# 1_P1.net
KiCad netlist of a schematic drawn in Altium Designer
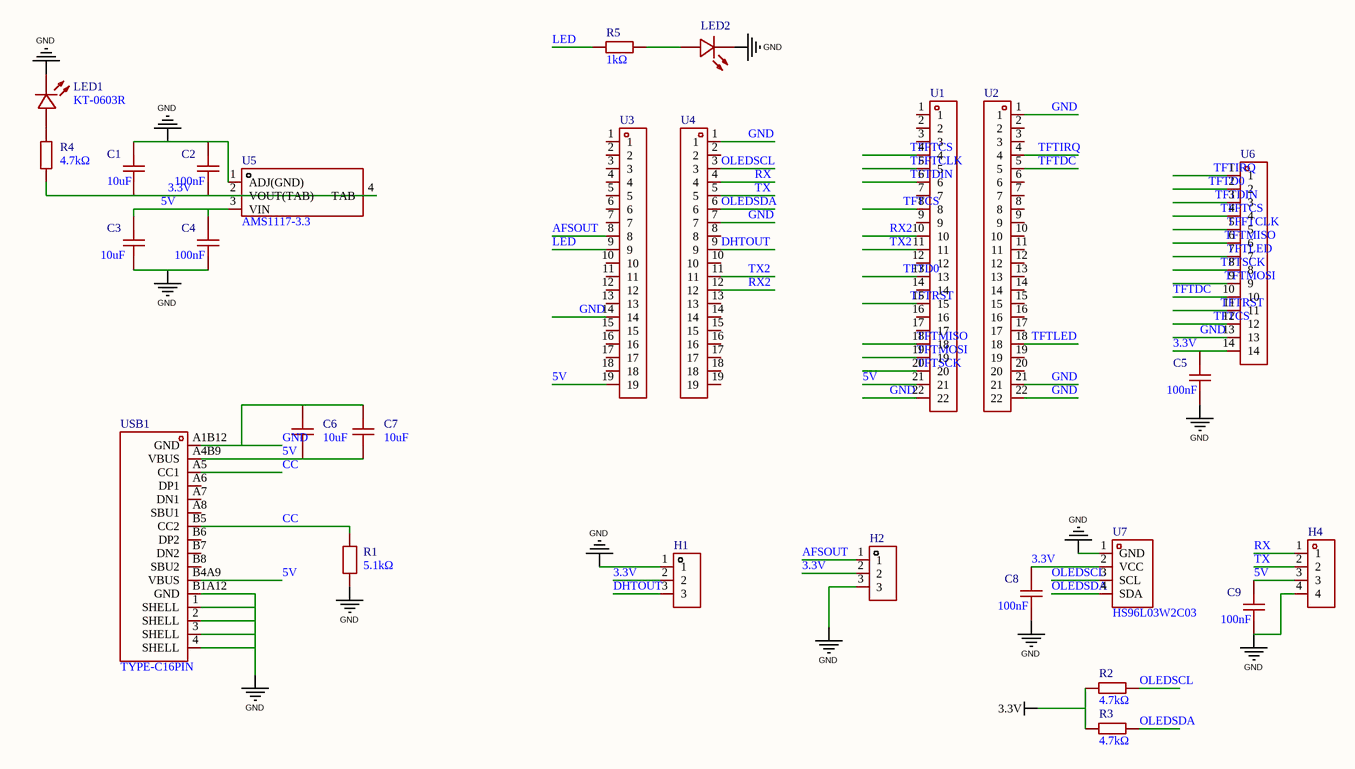
[diagram p0: 1_P1.schdoc]

(export (version "E")
  (design (tool "Eeschema 10.0.6"))
  (components
    (comp (ref "C1")
      (value "10uF")
      (footprint "C0603")
      (fields
        (field (name "MANUFACTURER") "SAMSUNG(三星)")
        (field (name "MANUFACTURER PART") "CL10A106KP8NNNC")
        (field (name "TOLERANCE") "±10%")
      )
      (libsource (lib "altium-import") (part "root_1_CL10A106KP8NNNC_"))
    )
    (comp (ref "C2")
      (value "100nF")
      (footprint "C0603")
      (fields
        (field (name "MANUFACTURER") "YAGEO(国巨)")
        (field (name "MANUFACTURER PART") "CC0603KRX7R9BB104")
        (field (name "TOLERANCE") "±10%")
      )
      (libsource (lib "altium-import") (part "root_1_CC0603KRX7R9BB104_"))
    )
    (comp (ref "C3")
      (value "10uF")
      (footprint "C0603")
      (fields
        (field (name "MANUFACTURER") "SAMSUNG(三星)")
        (field (name "MANUFACTURER PART") "CL10A106KP8NNNC")
        (field (name "TOLERANCE") "±10%")
      )
      (libsource (lib "altium-import") (part "root_1_CL10A106KP8NNNC_"))
    )
    (comp (ref "C4")
      (value "100nF")
      (footprint "C0603")
      (fields
        (field (name "MANUFACTURER") "YAGEO(国巨)")
        (field (name "MANUFACTURER PART") "CC0603KRX7R9BB104")
        (field (name "TOLERANCE") "±10%")
      )
      (libsource (lib "altium-import") (part "root_1_CC0603KRX7R9BB104_"))
    )
    (comp (ref "C5")
      (value "100nF")
      (footprint "C0603")
      (fields
        (field (name "MANUFACTURER") "YAGEO(国巨)")
        (field (name "MANUFACTURER PART") "CC0603KRX7R9BB104")
        (field (name "TOLERANCE") "±10%")
      )
      (libsource (lib "altium-import") (part "root_1_CC0603KRX7R9BB104_"))
    )
    (comp (ref "C6")
      (value "10uF")
      (footprint "C0603")
      (fields
        (field (name "MANUFACTURER") "SAMSUNG(三星)")
        (field (name "MANUFACTURER PART") "CL10A106KP8NNNC")
        (field (name "TOLERANCE") "±10%")
      )
      (libsource (lib "altium-import") (part "root_3_CL10A106KP8NNNC_"))
    )
    (comp (ref "C7")
      (value "10uF")
      (footprint "C0603")
      (fields
        (field (name "MANUFACTURER") "SAMSUNG(三星)")
        (field (name "MANUFACTURER PART") "CL10A106KP8NNNC")
        (field (name "TOLERANCE") "±10%")
      )
      (libsource (lib "altium-import") (part "root_3_CL10A106KP8NNNC_"))
    )
    (comp (ref "C8")
      (value "100nF")
      (footprint "C0603")
      (fields
        (field (name "MANUFACTURER") "YAGEO(国巨)")
        (field (name "MANUFACTURER PART") "CC0603KRX7R9BB104")
        (field (name "TOLERANCE") "±10%")
      )
      (libsource (lib "altium-import") (part "root_1_CC0603KRX7R9BB104_"))
    )
    (comp (ref "C9")
      (value "100nF")
      (footprint "C0603")
      (fields
        (field (name "MANUFACTURER") "YAGEO(国巨)")
        (field (name "MANUFACTURER PART") "CC0603KRX7R9BB104")
        (field (name "TOLERANCE") "±10%")
      )
      (libsource (lib "altium-import") (part "root_1_CC0603KRX7R9BB104_"))
    )
    (comp (ref "H1")
      (value "PM254V-11-03-H85")
      (footprint "HDR-TH_3P-P2.54-V-F")
      (fields (field (name "MANUFACTURER") "XFCN(兴飞)"))
      (libsource (lib "altium-import") (part "root_0_PM254V-11-03-H85_"))
    )
    (comp (ref "H2")
      (value "PM254V-11-03-H85")
      (footprint "HDR-TH_3P-P2.54-V-F")
      (fields (field (name "MANUFACTURER") "XFCN(兴飞)"))
      (libsource (lib "altium-import") (part "root_0_PM254V-11-03-H85_"))
    )
    (comp (ref "H4")
      (value "PZ254V-11-04P")
      (footprint "HDR-TH_4P-P2.54-V-M")
      (fields (field (name "MANUFACTURER") "XFCN(兴飞)"))
      (libsource (lib "altium-import") (part "root_0_PZ254V-11-04P_"))
    )
    (comp (ref "LED1")
      (value "KT-0603R")
      (footprint "LED0603-RD")
      (fields (field (name "MANUFACTURER") "KENTO"))
      (libsource (lib "altium-import") (part "root_3_KT-0603R_"))
    )
    (comp (ref "LED2")
      (value "KT-0603R")
      (footprint "LED0603-RD")
      (fields (field (name "MANUFACTURER") "KENTO"))
      (libsource (lib "altium-import") (part "root_2_KT-0603R_"))
    )
    (comp (ref "R1")
      (value "5.1kΩ")
      (footprint "R0603")
      (fields
        (field (name "MANUFACTURER") "FOJAN(富捷)")
        (field (name "MANUFACTURER PART") "FRC0603F5101TS")
        (field (name "TOLERANCE") "±1%")
      )
      (libsource (lib "altium-import") (part "root_1_mirrored_FRC0603F5101TS_"))
    )
    (comp (ref "R2")
      (value "4.7kΩ")
      (footprint "R0603")
      (fields
        (field (name "MANUFACTURER") "UNI-ROYAL(厚声)")
        (field (name "MANUFACTURER PART") "0603WAF4701T5E")
        (field (name "TOLERANCE") "±1%")
      )
      (libsource (lib "altium-import") (part "root_2_0603WAF4701T5E_"))
    )
    (comp (ref "R3")
      (value "4.7kΩ")
      (footprint "R0603")
      (fields
        (field (name "MANUFACTURER") "UNI-ROYAL(厚声)")
        (field (name "MANUFACTURER PART") "0603WAF4701T5E")
        (field (name "TOLERANCE") "±1%")
      )
      (libsource (lib "altium-import") (part "root_2_0603WAF4701T5E_"))
    )
    (comp (ref "R4")
      (value "4.7kΩ")
      (footprint "R0603")
      (fields
        (field (name "MANUFACTURER") "UNI-ROYAL(厚声)")
        (field (name "MANUFACTURER PART") "0603WAF4701T5E")
        (field (name "TOLERANCE") "±1%")
      )
      (libsource (lib "altium-import") (part "root_3_0603WAF4701T5E_"))
    )
    (comp (ref "R5")
      (value "1kΩ")
      (footprint "R0603")
      (fields
        (field (name "MANUFACTURER") "UNI-ROYAL(厚声)")
        (field (name "MANUFACTURER PART") "0603WAF1001T5E")
        (field (name "TOLERANCE") "±1%")
      )
      (libsource (lib "altium-import") (part "root_0_0603WAF1001T5E_"))
    )
    (comp (ref "U1")
      (value "ZX-PM2.54-1-22PY")
      (footprint "HDR-TH_22P-P2.54-V-F")
      (fields (field (name "MANUFACTURER") "Megastar(兆星)"))
      (libsource (lib "altium-import") (part "root_0_ZX-PM2.54-1-22PY_"))
    )
    (comp (ref "U2")
      (value "ZX-PM2.54-1-22PY")
      (footprint "HDR-TH_22P-P2.54-V-F")
      (fields (field (name "MANUFACTURER") "Megastar(兆星)"))
      (libsource (lib "altium-import") (part "root_0_mirrored_ZX-PM2.54-1-22PY_"))
    )
    (comp (ref "U3")
      (value "ZX-PM2.54-1-19PY")
      (footprint "HDR-TH_19P-P2.54-V-F")
      (fields (field (name "MANUFACTURER") "Megastar(兆星)"))
      (libsource (lib "altium-import") (part "root_0_ZX-PM2.54-1-19PY_"))
    )
    (comp (ref "U4")
      (value "ZX-PM2.54-1-19PY")
      (footprint "HDR-TH_19P-P2.54-V-F")
      (fields (field (name "MANUFACTURER") "Megastar(兆星)"))
      (libsource (lib "altium-import") (part "root_0_mirrored_ZX-PM2.54-1-19PY_"))
    )
    (comp (ref "U5")
      (value "AMS1117-3.3")
      (footprint "SOT-223-4_L6.5-W3.5-P2.30-LS7.0-BR")
      (fields (field (name "MANUFACTURER") "UMW(友台半导体)"))
      (libsource (lib "altium-import") (part "root_0_AMS1117-3.3_C347222_"))
    )
    (comp (ref "U6")
      (value "PM254-1-14-Z-8.5")
      (footprint "HDR-TH_14P-P2.54-V-F-1")
      (fields (field (name "MANUFACTURER") "HCTL(华灿天禄)"))
      (libsource (lib "altium-import") (part "root_0_PM254-1-14-Z-8.5_"))
    )
    (comp (ref "U7")
      (value "HS96L03W2C03")
      (footprint "OLED-TH_L27.8-W27.2-P2.54_C9900033791")
      (fields (field (name "MANUFACTURER") "HS(汉昇)"))
      (libsource (lib "altium-import") (part "root_0_HS96L03W2C03_"))
    )
    (comp (ref "USB1")
      (value "TYPE-C16PIN")
      (footprint "USB-C-SMD_TYPE-C16PIN")
      (fields (field (name "MANUFACTURER") "SHOU HAN(首韩)"))
      (libsource (lib "altium-import") (part "root_0_mirrored_TYPE-C16PIN_"))
    )
  )
  (nets
    (net (code "1") (name "/5V") (class "Default")
      (node (ref "C3") (pin "2") (pinfunction "2_2") (pintype "passive"))
      (node (ref "C4") (pin "2") (pinfunction "2_2") (pintype "passive"))
      (node (ref "C6") (pin "2") (pinfunction "2_2") (pintype "passive"))
      (node (ref "C7") (pin "2") (pinfunction "2_2") (pintype "passive"))
      (node (ref "C9") (pin "2") (pinfunction "2_2") (pintype "passive"))
      (node (ref "H4") (pin "3") (pinfunction "3_3") (pintype "passive"))
      (node (ref "U1") (pin "21") (pinfunction "21_21") (pintype "passive"))
      (node (ref "U3") (pin "19") (pinfunction "19_19") (pintype "passive"))
      (node (ref "U5") (pin "3") (pinfunction "VIN_3") (pintype "passive"))
      (node (ref "USB1") (pin "A4B9") (pinfunction "VBUS_A4B9") (pintype "passive"))
      (node (ref "USB1") (pin "B4A9") (pinfunction "VBUS_B4A9") (pintype "passive"))
    )
    (net (code "2") (name "/AFSOUT") (class "Default")
      (node (ref "H2") (pin "1") (pinfunction "1_1") (pintype "passive"))
      (node (ref "U3") (pin "8") (pinfunction "8_8") (pintype "passive"))
    )
    (net (code "3") (name "/CC") (class "Default")
      (node (ref "R1") (pin "2") (pinfunction "2_2") (pintype "passive"))
      (node (ref "USB1") (pin "A5") (pinfunction "CC1_A5") (pintype "passive"))
      (node (ref "USB1") (pin "B5") (pinfunction "CC2_B5") (pintype "passive"))
    )
    (net (code "4") (name "/DHTOUT") (class "Default")
      (node (ref "H1") (pin "3") (pinfunction "3_3") (pintype "passive"))
      (node (ref "U4") (pin "9") (pinfunction "9_9") (pintype "passive"))
    )
    (net (code "5") (name "/LED") (class "Default")
      (node (ref "R5") (pin "1") (pinfunction "1_1") (pintype "passive"))
      (node (ref "U3") (pin "9") (pinfunction "9_9") (pintype "passive"))
    )
    (net (code "6") (name "/OLEDSCL") (class "Default")
      (node (ref "R2") (pin "1") (pinfunction "1_1") (pintype "passive"))
      (node (ref "U4") (pin "3") (pinfunction "3_3") (pintype "passive"))
      (node (ref "U7") (pin "3") (pinfunction "SCL_3") (pintype "passive"))
    )
    (net (code "7") (name "/OLEDSDA") (class "Default")
      (node (ref "R3") (pin "1") (pinfunction "1_1") (pintype "passive"))
      (node (ref "U4") (pin "6") (pinfunction "6_6") (pintype "passive"))
      (node (ref "U7") (pin "4") (pinfunction "SDA_4") (pintype "passive"))
    )
    (net (code "8") (name "/RX") (class "Default")
      (node (ref "H4") (pin "1") (pinfunction "1_1") (pintype "passive"))
      (node (ref "U4") (pin "4") (pinfunction "4_4") (pintype "passive"))
    )
    (net (code "9") (name "/RX2") (class "Default")
      (node (ref "U1") (pin "10") (pinfunction "10_10") (pintype "passive"))
      (node (ref "U4") (pin "12") (pinfunction "12_12") (pintype "passive"))
    )
    (net (code "10") (name "/TFFTCLK") (class "Default")
      (node (ref "U1") (pin "5") (pinfunction "5_5") (pintype "passive"))
      (node (ref "U6") (pin "5") (pinfunction "5_5") (pintype "passive"))
    )
    (net (code "11") (name "/TFFTCS") (class "Default")
      (node (ref "U1") (pin "4") (pinfunction "4_4") (pintype "passive"))
      (node (ref "U6") (pin "4") (pinfunction "4_4") (pintype "passive"))
    )
    (net (code "12") (name "/TFTCS") (class "Default")
      (node (ref "U1") (pin "8") (pinfunction "8_8") (pintype "passive"))
      (node (ref "U6") (pin "12") (pinfunction "12_12") (pintype "passive"))
    )
    (net (code "13") (name "/TFTD0") (class "Default")
      (node (ref "U1") (pin "13") (pinfunction "13_13") (pintype "passive"))
      (node (ref "U6") (pin "2") (pinfunction "2_2") (pintype "passive"))
    )
    (net (code "14") (name "/TFTDC") (class "Default")
      (node (ref "U2") (pin "5") (pinfunction "5_5") (pintype "passive"))
      (node (ref "U6") (pin "10") (pinfunction "10_10") (pintype "passive"))
    )
    (net (code "15") (name "/TFTDIN") (class "Default")
      (node (ref "U1") (pin "6") (pinfunction "6_6") (pintype "passive"))
      (node (ref "U6") (pin "3") (pinfunction "3_3") (pintype "passive"))
    )
    (net (code "16") (name "/TFTIRQ") (class "Default")
      (node (ref "U2") (pin "4") (pinfunction "4_4") (pintype "passive"))
      (node (ref "U6") (pin "1") (pinfunction "1_1") (pintype "passive"))
    )
    (net (code "17") (name "/TFTLED") (class "Default")
      (node (ref "U2") (pin "18") (pinfunction "18_18") (pintype "passive"))
      (node (ref "U6") (pin "7") (pinfunction "7_7") (pintype "passive"))
    )
    (net (code "18") (name "/TFTMISO") (class "Default")
      (node (ref "U1") (pin "18") (pinfunction "18_18") (pintype "passive"))
      (node (ref "U6") (pin "6") (pinfunction "6_6") (pintype "passive"))
    )
    (net (code "19") (name "/TFTMOSI") (class "Default")
      (node (ref "U1") (pin "19") (pinfunction "19_19") (pintype "passive"))
      (node (ref "U6") (pin "9") (pinfunction "9_9") (pintype "passive"))
    )
    (net (code "20") (name "/TFTRST") (class "Default")
      (node (ref "U1") (pin "15") (pinfunction "15_15") (pintype "passive"))
      (node (ref "U6") (pin "11") (pinfunction "11_11") (pintype "passive"))
    )
    (net (code "21") (name "/TFTSCK") (class "Default")
      (node (ref "U1") (pin "20") (pinfunction "20_20") (pintype "passive"))
      (node (ref "U6") (pin "8") (pinfunction "8_8") (pintype "passive"))
    )
    (net (code "22") (name "/TX") (class "Default")
      (node (ref "H4") (pin "2") (pinfunction "2_2") (pintype "passive"))
      (node (ref "U4") (pin "5") (pinfunction "5_5") (pintype "passive"))
    )
    (net (code "23") (name "/TX2") (class "Default")
      (node (ref "U1") (pin "11") (pinfunction "11_11") (pintype "passive"))
      (node (ref "U4") (pin "11") (pinfunction "11_11") (pintype "passive"))
    )
    (net (code "24") (name "3.3V") (class "Default")
      (node (ref "C1") (pin "1") (pinfunction "1_1") (pintype "passive"))
      (node (ref "C2") (pin "1") (pinfunction "1_1") (pintype "passive"))
      (node (ref "C5") (pin "2") (pinfunction "2_2") (pintype "passive"))
      (node (ref "C8") (pin "2") (pinfunction "2_2") (pintype "passive"))
      (node (ref "H1") (pin "2") (pinfunction "2_2") (pintype "passive"))
      (node (ref "H2") (pin "2") (pinfunction "2_2") (pintype "passive"))
      (node (ref "R2") (pin "2") (pinfunction "2_2") (pintype "passive"))
      (node (ref "R3") (pin "2") (pinfunction "2_2") (pintype "passive"))
      (node (ref "R4") (pin "2") (pinfunction "2_2") (pintype "passive"))
      (node (ref "U5") (pin "2") (pinfunction "VOUT(TAB)_2") (pintype "passive"))
      (node (ref "U5") (pin "4") (pinfunction "TAB_4") (pintype "passive"))
      (node (ref "U6") (pin "14") (pinfunction "14_14") (pintype "passive"))
      (node (ref "U7") (pin "2") (pinfunction "VCC_2") (pintype "passive"))
    )
    (net (code "25") (name "GND") (class "Default")
      (node (ref "C1") (pin "2") (pinfunction "2_2") (pintype "passive"))
      (node (ref "C2") (pin "2") (pinfunction "2_2") (pintype "passive"))
      (node (ref "C3") (pin "1") (pinfunction "1_1") (pintype "passive"))
      (node (ref "C4") (pin "1") (pinfunction "1_1") (pintype "passive"))
      (node (ref "C5") (pin "1") (pinfunction "1_1") (pintype "passive"))
      (node (ref "C6") (pin "1") (pinfunction "1_1") (pintype "passive"))
      (node (ref "C7") (pin "1") (pinfunction "1_1") (pintype "passive"))
      (node (ref "C8") (pin "1") (pinfunction "1_1") (pintype "passive"))
      (node (ref "C9") (pin "1") (pinfunction "1_1") (pintype "passive"))
      (node (ref "H1") (pin "1") (pinfunction "1_1") (pintype "passive"))
      (node (ref "H2") (pin "3") (pinfunction "3_3") (pintype "passive"))
      (node (ref "H4") (pin "4") (pinfunction "4_4") (pintype "passive"))
      (node (ref "LED1") (pin "1") (pinfunction "K_1") (pintype "passive"))
      (node (ref "LED2") (pin "1") (pinfunction "K_1") (pintype "passive"))
      (node (ref "R1") (pin "1") (pinfunction "1_1") (pintype "passive"))
      (node (ref "U1") (pin "22") (pinfunction "22_22") (pintype "passive"))
      (node (ref "U2") (pin "1") (pinfunction "1_1") (pintype "passive"))
      (node (ref "U2") (pin "21") (pinfunction "21_21") (pintype "passive"))
      (node (ref "U2") (pin "22") (pinfunction "22_22") (pintype "passive"))
      (node (ref "U3") (pin "14") (pinfunction "14_14") (pintype "passive"))
      (node (ref "U4") (pin "1") (pinfunction "1_1") (pintype "passive"))
      (node (ref "U4") (pin "7") (pinfunction "7_7") (pintype "passive"))
      (node (ref "U5") (pin "1") (pinfunction "ADJ(GND)_1") (pintype "passive"))
      (node (ref "U6") (pin "13") (pinfunction "13_13") (pintype "passive"))
      (node (ref "U7") (pin "1") (pinfunction "GND_1") (pintype "passive"))
      (node (ref "USB1") (pin "1") (pinfunction "SHELL_1") (pintype "passive"))
      (node (ref "USB1") (pin "2") (pinfunction "SHELL_2") (pintype "passive"))
      (node (ref "USB1") (pin "3") (pinfunction "SHELL_3") (pintype "passive"))
      (node (ref "USB1") (pin "4") (pinfunction "SHELL_4") (pintype "passive"))
      (node (ref "USB1") (pin "A1B12") (pinfunction "GND_A1B12") (pintype "passive"))
      (node (ref "USB1") (pin "B1A12") (pinfunction "GND_B1A12") (pintype "passive"))
    )
    (net (code "26") (name "Net-(LED1-A)") (class "Default")
      (node (ref "LED1") (pin "2") (pinfunction "A_2") (pintype "passive"))
      (node (ref "R4") (pin "1") (pinfunction "1_1") (pintype "passive"))
    )
    (net (code "27") (name "Net-(LED2-A)") (class "Default")
      (node (ref "LED2") (pin "2") (pinfunction "A_2") (pintype "passive"))
      (node (ref "R5") (pin "2") (pinfunction "2_2") (pintype "passive"))
    )
    (net (code "28") (name "unconnected-(U1-Pad1)") (class "Default")
      (node (ref "U1") (pin "1") (pinfunction "1_1") (pintype "passive"))
    )
    (net (code "29") (name "unconnected-(U1-Pad2)") (class "Default")
      (node (ref "U1") (pin "2") (pinfunction "2_2") (pintype "passive"))
    )
    (net (code "30") (name "unconnected-(U1-Pad3)") (class "Default")
      (node (ref "U1") (pin "3") (pinfunction "3_3") (pintype "passive"))
    )
    (net (code "31") (name "unconnected-(U1-Pad7)") (class "Default")
      (node (ref "U1") (pin "7") (pinfunction "7_7") (pintype "passive"))
    )
    (net (code "32") (name "unconnected-(U1-Pad9)") (class "Default")
      (node (ref "U1") (pin "9") (pinfunction "9_9") (pintype "passive"))
    )
    (net (code "33") (name "unconnected-(U1-Pad12)") (class "Default")
      (node (ref "U1") (pin "12") (pinfunction "12_12") (pintype "passive"))
    )
    (net (code "34") (name "unconnected-(U1-Pad14)") (class "Default")
      (node (ref "U1") (pin "14") (pinfunction "14_14") (pintype "passive"))
    )
    (net (code "35") (name "unconnected-(U1-Pad16)") (class "Default")
      (node (ref "U1") (pin "16") (pinfunction "16_16") (pintype "passive"))
    )
    (net (code "36") (name "unconnected-(U1-Pad17)") (class "Default")
      (node (ref "U1") (pin "17") (pinfunction "17_17") (pintype "passive"))
    )
    (net (code "37") (name "unconnected-(U2-Pad2)") (class "Default")
      (node (ref "U2") (pin "2") (pinfunction "2_2") (pintype "passive"))
    )
    (net (code "38") (name "unconnected-(U2-Pad3)") (class "Default")
      (node (ref "U2") (pin "3") (pinfunction "3_3") (pintype "passive"))
    )
    (net (code "39") (name "unconnected-(U2-Pad6)") (class "Default")
      (node (ref "U2") (pin "6") (pinfunction "6_6") (pintype "passive"))
    )
    (net (code "40") (name "unconnected-(U2-Pad7)") (class "Default")
      (node (ref "U2") (pin "7") (pinfunction "7_7") (pintype "passive"))
    )
    (net (code "41") (name "unconnected-(U2-Pad8)") (class "Default")
      (node (ref "U2") (pin "8") (pinfunction "8_8") (pintype "passive"))
    )
    (net (code "42") (name "unconnected-(U2-Pad9)") (class "Default")
      (node (ref "U2") (pin "9") (pinfunction "9_9") (pintype "passive"))
    )
    (net (code "43") (name "unconnected-(U2-Pad10)") (class "Default")
      (node (ref "U2") (pin "10") (pinfunction "10_10") (pintype "passive"))
    )
    (net (code "44") (name "unconnected-(U2-Pad11)") (class "Default")
      (node (ref "U2") (pin "11") (pinfunction "11_11") (pintype "passive"))
    )
    (net (code "45") (name "unconnected-(U2-Pad12)") (class "Default")
      (node (ref "U2") (pin "12") (pinfunction "12_12") (pintype "passive"))
    )
    (net (code "46") (name "unconnected-(U2-Pad13)") (class "Default")
      (node (ref "U2") (pin "13") (pinfunction "13_13") (pintype "passive"))
    )
    (net (code "47") (name "unconnected-(U2-Pad14)") (class "Default")
      (node (ref "U2") (pin "14") (pinfunction "14_14") (pintype "passive"))
    )
    (net (code "48") (name "unconnected-(U2-Pad15)") (class "Default")
      (node (ref "U2") (pin "15") (pinfunction "15_15") (pintype "passive"))
    )
    (net (code "49") (name "unconnected-(U2-Pad16)") (class "Default")
      (node (ref "U2") (pin "16") (pinfunction "16_16") (pintype "passive"))
    )
    (net (code "50") (name "unconnected-(U2-Pad17)") (class "Default")
      (node (ref "U2") (pin "17") (pinfunction "17_17") (pintype "passive"))
    )
    (net (code "51") (name "unconnected-(U2-Pad19)") (class "Default")
      (node (ref "U2") (pin "19") (pinfunction "19_19") (pintype "passive"))
    )
    (net (code "52") (name "unconnected-(U2-Pad20)") (class "Default")
      (node (ref "U2") (pin "20") (pinfunction "20_20") (pintype "passive"))
    )
    (net (code "53") (name "unconnected-(U3-Pad1)") (class "Default")
      (node (ref "U3") (pin "1") (pinfunction "1_1") (pintype "passive"))
    )
    (net (code "54") (name "unconnected-(U3-Pad2)") (class "Default")
      (node (ref "U3") (pin "2") (pinfunction "2_2") (pintype "passive"))
    )
    (net (code "55") (name "unconnected-(U3-Pad3)") (class "Default")
      (node (ref "U3") (pin "3") (pinfunction "3_3") (pintype "passive"))
    )
    (net (code "56") (name "unconnected-(U3-Pad4)") (class "Default")
      (node (ref "U3") (pin "4") (pinfunction "4_4") (pintype "passive"))
    )
    (net (code "57") (name "unconnected-(U3-Pad5)") (class "Default")
      (node (ref "U3") (pin "5") (pinfunction "5_5") (pintype "passive"))
    )
    (net (code "58") (name "unconnected-(U3-Pad6)") (class "Default")
      (node (ref "U3") (pin "6") (pinfunction "6_6") (pintype "passive"))
    )
    (net (code "59") (name "unconnected-(U3-Pad7)") (class "Default")
      (node (ref "U3") (pin "7") (pinfunction "7_7") (pintype "passive"))
    )
    (net (code "60") (name "unconnected-(U3-Pad10)") (class "Default")
      (node (ref "U3") (pin "10") (pinfunction "10_10") (pintype "passive"))
    )
    (net (code "61") (name "unconnected-(U3-Pad11)") (class "Default")
      (node (ref "U3") (pin "11") (pinfunction "11_11") (pintype "passive"))
    )
    (net (code "62") (name "unconnected-(U3-Pad12)") (class "Default")
      (node (ref "U3") (pin "12") (pinfunction "12_12") (pintype "passive"))
    )
    (net (code "63") (name "unconnected-(U3-Pad13)") (class "Default")
      (node (ref "U3") (pin "13") (pinfunction "13_13") (pintype "passive"))
    )
    (net (code "64") (name "unconnected-(U3-Pad15)") (class "Default")
      (node (ref "U3") (pin "15") (pinfunction "15_15") (pintype "passive"))
    )
    (net (code "65") (name "unconnected-(U3-Pad16)") (class "Default")
      (node (ref "U3") (pin "16") (pinfunction "16_16") (pintype "passive"))
    )
    (net (code "66") (name "unconnected-(U3-Pad17)") (class "Default")
      (node (ref "U3") (pin "17") (pinfunction "17_17") (pintype "passive"))
    )
    (net (code "67") (name "unconnected-(U3-Pad18)") (class "Default")
      (node (ref "U3") (pin "18") (pinfunction "18_18") (pintype "passive"))
    )
    (net (code "68") (name "unconnected-(U4-Pad2)") (class "Default")
      (node (ref "U4") (pin "2") (pinfunction "2_2") (pintype "passive"))
    )
    (net (code "69") (name "unconnected-(U4-Pad8)") (class "Default")
      (node (ref "U4") (pin "8") (pinfunction "8_8") (pintype "passive"))
    )
    (net (code "70") (name "unconnected-(U4-Pad10)") (class "Default")
      (node (ref "U4") (pin "10") (pinfunction "10_10") (pintype "passive"))
    )
    (net (code "71") (name "unconnected-(U4-Pad13)") (class "Default")
      (node (ref "U4") (pin "13") (pinfunction "13_13") (pintype "passive"))
    )
    (net (code "72") (name "unconnected-(U4-Pad14)") (class "Default")
      (node (ref "U4") (pin "14") (pinfunction "14_14") (pintype "passive"))
    )
    (net (code "73") (name "unconnected-(U4-Pad15)") (class "Default")
      (node (ref "U4") (pin "15") (pinfunction "15_15") (pintype "passive"))
    )
    (net (code "74") (name "unconnected-(U4-Pad16)") (class "Default")
      (node (ref "U4") (pin "16") (pinfunction "16_16") (pintype "passive"))
    )
    (net (code "75") (name "unconnected-(U4-Pad17)") (class "Default")
      (node (ref "U4") (pin "17") (pinfunction "17_17") (pintype "passive"))
    )
    (net (code "76") (name "unconnected-(U4-Pad18)") (class "Default")
      (node (ref "U4") (pin "18") (pinfunction "18_18") (pintype "passive"))
    )
    (net (code "77") (name "unconnected-(U4-Pad19)") (class "Default")
      (node (ref "U4") (pin "19") (pinfunction "19_19") (pintype "passive"))
    )
    (net (code "78") (name "unconnected-(USB1-DN1-PadA7)") (class "Default")
      (node (ref "USB1") (pin "A7") (pinfunction "DN1_A7") (pintype "passive"))
    )
    (net (code "79") (name "unconnected-(USB1-DN2-PadB7)") (class "Default")
      (node (ref "USB1") (pin "B7") (pinfunction "DN2_B7") (pintype "passive"))
    )
    (net (code "80") (name "unconnected-(USB1-DP1-PadA6)") (class "Default")
      (node (ref "USB1") (pin "A6") (pinfunction "DP1_A6") (pintype "passive"))
    )
    (net (code "81") (name "unconnected-(USB1-DP2-PadB6)") (class "Default")
      (node (ref "USB1") (pin "B6") (pinfunction "DP2_B6") (pintype "passive"))
    )
    (net (code "82") (name "unconnected-(USB1-SBU1-PadA8)") (class "Default")
      (node (ref "USB1") (pin "A8") (pinfunction "SBU1_A8") (pintype "passive"))
    )
    (net (code "83") (name "unconnected-(USB1-SBU2-PadB8)") (class "Default")
      (node (ref "USB1") (pin "B8") (pinfunction "SBU2_B8") (pintype "passive"))
    )
  )
)
